# picoclick_c3t.net
KiCad netlist of a schematic drawn in EAGLE
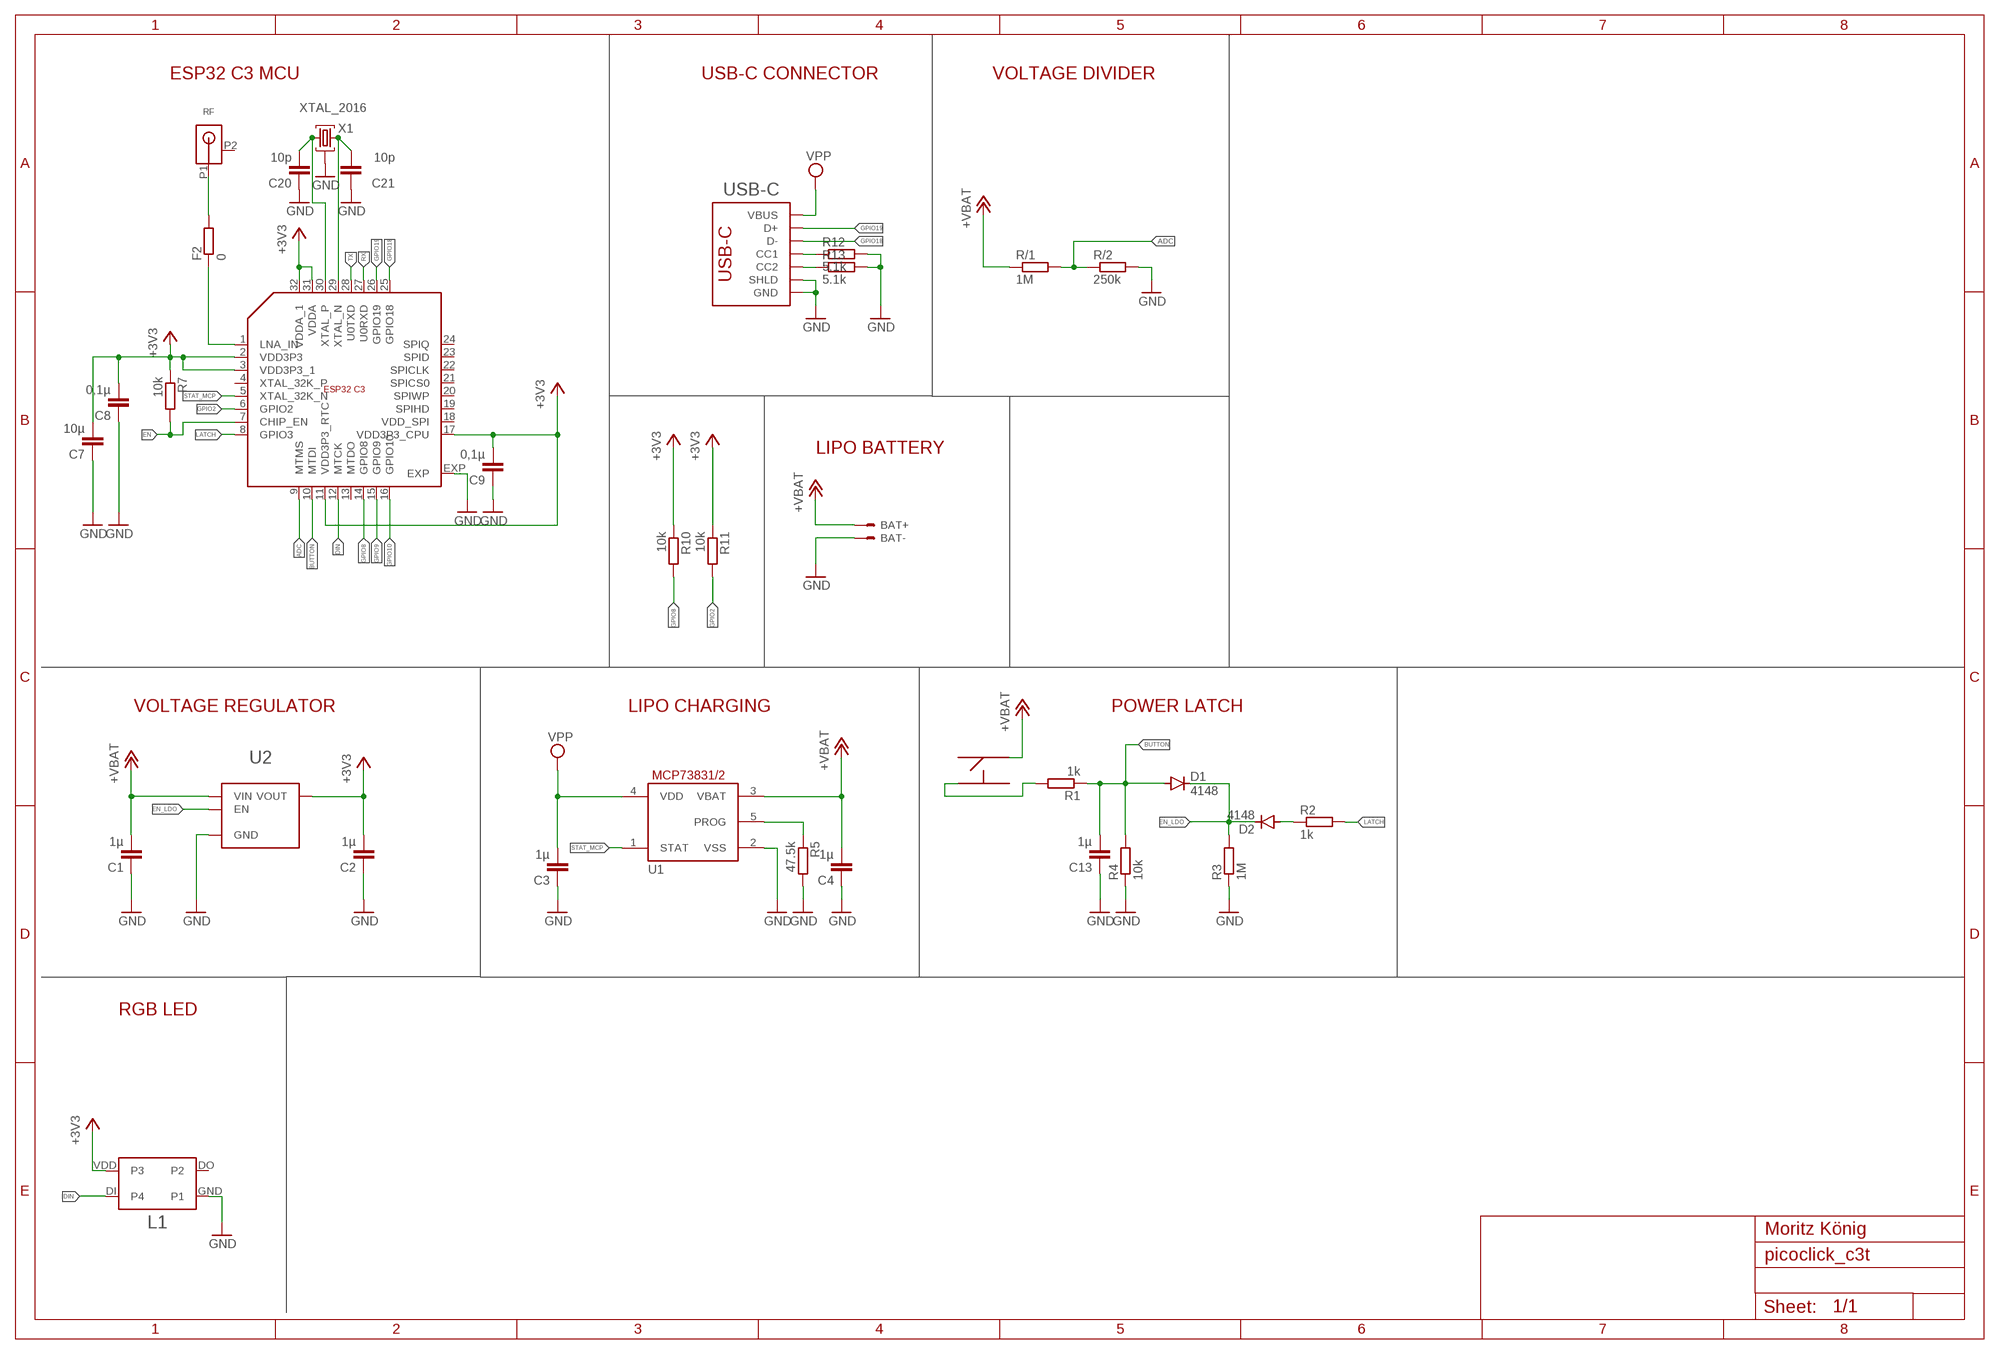
[diagram p0: schematic, sheet 1]

(export (version "E")
  (design (tool "Eeschema 10.0.6"))
  (components
    (comp (ref "BAT+")
      (value "TP/SP-1.5X1.0")
      (footprint "eagle-import:SOLDERPAD_1.5X1.0")
      (libsource (lib "eagle-import") (part "TP/SP-1.5X1.0"))
    )
    (comp (ref "BAT-")
      (value "TP/SP-1.5X1.0")
      (footprint "eagle-import:SOLDERPAD_1.5X1.0")
      (libsource (lib "eagle-import") (part "TP/SP-1.5X1.0"))
    )
    (comp (ref "C1")
      (value "1µ")
      (footprint "eagle-import:C0402_S")
      (libsource (lib "eagle-import") (part "C-EU-0402-WOKEEPOUT_S"))
    )
    (comp (ref "C2")
      (value "1µ")
      (footprint "eagle-import:C0402_S")
      (libsource (lib "eagle-import") (part "C-EU-0402-WOKEEPOUT_S"))
    )
    (comp (ref "C3")
      (value "1µ")
      (footprint "eagle-import:C0402_S")
      (libsource (lib "eagle-import") (part "C-EU-0402-WOKEEPOUT_S"))
    )
    (comp (ref "C4")
      (value "1µ")
      (footprint "eagle-import:C0402_S")
      (libsource (lib "eagle-import") (part "C-EU-0402-WOKEEPOUT_S"))
    )
    (comp (ref "C7")
      (value "10µ")
      (footprint "eagle-import:C0402_S")
      (libsource (lib "eagle-import") (part "C-EU-0402-WOKEEPOUT_S"))
    )
    (comp (ref "C8")
      (value "0,1µ")
      (footprint "eagle-import:C0402_S")
      (libsource (lib "eagle-import") (part "C-EU-0402-WOKEEPOUT_S"))
    )
    (comp (ref "C9")
      (value "0,1µ")
      (footprint "eagle-import:C0402_S")
      (libsource (lib "eagle-import") (part "C-EU-0402-WOKEEPOUT_S"))
    )
    (comp (ref "C13")
      (value "1µ")
      (footprint "eagle-import:C0402_S")
      (libsource (lib "eagle-import") (part "C-EU-0402-WOKEEPOUT_S"))
    )
    (comp (ref "C20")
      (value "10p")
      (footprint "eagle-import:C0402_S")
      (libsource (lib "eagle-import") (part "C-EU-0402-WOKEEPOUT_S"))
    )
    (comp (ref "C21")
      (value "10p")
      (footprint "eagle-import:C0402_S")
      (libsource (lib "eagle-import") (part "C-EU-0402-WOKEEPOUT_S"))
    )
    (comp (ref "D1")
      (value "4148")
      (footprint "eagle-import:SOD523")
      (libsource (lib "eagle-import") (part "DIODE-SOD523"))
    )
    (comp (ref "D2")
      (value "4148")
      (footprint "eagle-import:SOD523")
      (libsource (lib "eagle-import") (part "DIODE-SOD523"))
    )
    (comp (ref "ESP1")
      (value "ESP32_C3_QFN32")
      (footprint "eagle-import:QFN32")
      (libsource (lib "eagle-import") (part "ESP32_C3_QFN32"))
    )
    (comp (ref "F2")
      (value "0")
      (footprint "eagle-import:R0402")
      (libsource (lib "eagle-import") (part "R-EU-0402-WOKEEPOUT"))
    )
    (comp (ref "L1")
      (value "WS2812_2020")
      (footprint "eagle-import:WS2812_2020")
      (libsource (lib "eagle-import") (part "WS2812_2020"))
    )
    (comp (ref "R/1")
      (value "1M")
      (footprint "eagle-import:R0402")
      (libsource (lib "eagle-import") (part "R-EU-0402-WOKEEPOUT"))
    )
    (comp (ref "R/2")
      (value "250k")
      (footprint "eagle-import:R0402")
      (libsource (lib "eagle-import") (part "R-EU-0402-WOKEEPOUT"))
    )
    (comp (ref "R1")
      (value "1k")
      (footprint "eagle-import:R0402")
      (libsource (lib "eagle-import") (part "R-EU-0402-WOKEEPOUT"))
    )
    (comp (ref "R2")
      (value "1k")
      (footprint "eagle-import:R0402")
      (libsource (lib "eagle-import") (part "R-EU-0402-WOKEEPOUT"))
    )
    (comp (ref "R3")
      (value "1M")
      (footprint "eagle-import:R0402")
      (libsource (lib "eagle-import") (part "R-EU-0402-WOKEEPOUT"))
    )
    (comp (ref "R4")
      (value "10k")
      (footprint "eagle-import:R0402")
      (libsource (lib "eagle-import") (part "R-EU-0402-WOKEEPOUT"))
    )
    (comp (ref "R5")
      (value "47.5k")
      (footprint "eagle-import:R0402")
      (libsource (lib "eagle-import") (part "R-EU-0402-WOKEEPOUT"))
    )
    (comp (ref "R7")
      (value "10k")
      (footprint "eagle-import:R0402")
      (libsource (lib "eagle-import") (part "R-EU-0402-WOKEEPOUT"))
    )
    (comp (ref "R10")
      (value "10k")
      (footprint "eagle-import:R0402")
      (libsource (lib "eagle-import") (part "R-EU-0402-WOKEEPOUT"))
    )
    (comp (ref "R11")
      (value "10k")
      (footprint "eagle-import:R0402")
      (libsource (lib "eagle-import") (part "R-EU-0402-WOKEEPOUT"))
    )
    (comp (ref "R12")
      (value "5.1k")
      (footprint "eagle-import:R0402")
      (libsource (lib "eagle-import") (part "R-EU-0402-WOKEEPOUT"))
    )
    (comp (ref "R13")
      (value "5.1k")
      (footprint "eagle-import:R0402")
      (libsource (lib "eagle-import") (part "R-EU-0402-WOKEEPOUT"))
    )
    (comp (ref "RF")
      (value "ANT3216LL00R2400A")
      (footprint "eagle-import:ANT3216LL00R2400A")
      (libsource (lib "eagle-import") (part "ANT3216LL00R2400A"))
    )
    (comp (ref "U$1")
      (value "BUTTON_ST-1187-3")
      (footprint "eagle-import:BUTTON_ST-1187-3")
      (libsource (lib "eagle-import") (part "BUTTON_ST-1187-3"))
    )
    (comp (ref "U1")
      (value "BRCL4054BME")
      (footprint "eagle-import:SOT23-5")
      (libsource (lib "eagle-import") (part "MCP73831_SOT23_5"))
    )
    (comp (ref "U2")
      (value "MIC5504")
      (footprint "eagle-import:TDFN4")
      (libsource (lib "eagle-import") (part "MIC5504"))
    )
    (comp (ref "USB-C")
      (value "USB_C_C393939")
      (footprint "eagle-import:USBC_C393939")
      (libsource (lib "eagle-import") (part "USB_C_C393939"))
    )
    (comp (ref "X1")
      (value "XTAL_2016")
      (footprint "eagle-import:XTYL_2016")
      (libsource (lib "eagle-import") (part "XTAL_2016"))
    )
  )
  (nets
    (net (code "1") (name "+3V3") (class "Default")
      (node (ref "C2") (pin "P$2") (pinfunction "2_P$2") (pintype "passive"))
      (node (ref "C7") (pin "P$2") (pinfunction "2_P$2") (pintype "passive"))
      (node (ref "C8") (pin "P$2") (pinfunction "2_P$2") (pintype "passive"))
      (node (ref "C9") (pin "P$2") (pinfunction "2_P$2") (pintype "passive"))
      (node (ref "ESP1") (pin "11") (pinfunction "VDD3P3_RTC_11") (pintype "bidirectional"))
      (node (ref "ESP1") (pin "17") (pinfunction "VDD3P3_CPU_17") (pintype "bidirectional"))
      (node (ref "ESP1") (pin "2") (pinfunction "VDD3P3_2") (pintype "bidirectional"))
      (node (ref "ESP1") (pin "3") (pinfunction "VDD3P3_1_3") (pintype "bidirectional"))
      (node (ref "ESP1") (pin "31") (pinfunction "VDDA_31") (pintype "bidirectional"))
      (node (ref "ESP1") (pin "32") (pinfunction "VDDA_1_32") (pintype "bidirectional"))
      (node (ref "L1") (pin "VDD") (pinfunction "P3_VDD") (pintype "bidirectional"))
      (node (ref "R10") (pin "1") (pinfunction "1_1") (pintype "passive"))
      (node (ref "R11") (pin "1") (pinfunction "1_1") (pintype "passive"))
      (node (ref "R7") (pin "1") (pinfunction "1_1") (pintype "passive"))
      (node (ref "U2") (pin "P1") (pinfunction "VOUT_P1") (pintype "bidirectional"))
    )
    (net (code "2") (name "+VBAT") (class "Default")
      (node (ref "BAT+") (pin "1") (pinfunction "S_1") (pintype "passive"))
      (node (ref "C1") (pin "P$2") (pinfunction "2_P$2") (pintype "passive"))
      (node (ref "C4") (pin "P$2") (pinfunction "2_P$2") (pintype "passive"))
      (node (ref "R/1") (pin "1") (pinfunction "1_1") (pintype "passive"))
      (node (ref "U$1") (pin "P2") (pinfunction "P2_P2") (pintype "bidirectional"))
      (node (ref "U1") (pin "3") (pinfunction "VBAT_3") (pintype "bidirectional"))
      (node (ref "U2") (pin "P4") (pinfunction "VIN_P4") (pintype "bidirectional"))
    )
    (net (code "3") (name "ADC") (class "Default")
      (node (ref "ESP1") (pin "9") (pinfunction "MTMS_9") (pintype "bidirectional"))
      (node (ref "R/1") (pin "2") (pinfunction "2_2") (pintype "passive"))
      (node (ref "R/2") (pin "1") (pinfunction "1_1") (pintype "passive"))
    )
    (net (code "4") (name "BUTTON") (class "Default")
      (node (ref "C13") (pin "P$2") (pinfunction "2_P$2") (pintype "passive"))
      (node (ref "D1") (pin "A") (pinfunction "A_A") (pintype "passive"))
      (node (ref "ESP1") (pin "10") (pinfunction "MTDI_10") (pintype "bidirectional"))
      (node (ref "R1") (pin "1") (pinfunction "1_1") (pintype "passive"))
      (node (ref "R4") (pin "2") (pinfunction "2_2") (pintype "passive"))
    )
    (net (code "5") (name "DIN") (class "Default")
      (node (ref "ESP1") (pin "12") (pinfunction "MTCK_12") (pintype "bidirectional"))
      (node (ref "L1") (pin "DI") (pinfunction "P4_DI") (pintype "bidirectional"))
    )
    (net (code "6") (name "EN") (class "Default")
      (node (ref "ESP1") (pin "7") (pinfunction "CHIP_EN_7") (pintype "bidirectional"))
      (node (ref "R7") (pin "2") (pinfunction "2_2") (pintype "passive"))
    )
    (net (code "7") (name "EN_LDO") (class "Default")
      (node (ref "D1") (pin "C") (pinfunction "C_C") (pintype "passive"))
      (node (ref "D2") (pin "C") (pinfunction "C_C") (pintype "passive"))
      (node (ref "R3") (pin "2") (pinfunction "2_2") (pintype "passive"))
      (node (ref "U2") (pin "P3") (pinfunction "EN_P3") (pintype "bidirectional"))
    )
    (net (code "8") (name "GND") (class "Default")
      (node (ref "BAT-") (pin "1") (pinfunction "S_1") (pintype "passive"))
      (node (ref "C1") (pin "P$1") (pinfunction "1_P$1") (pintype "passive"))
      (node (ref "C13") (pin "P$1") (pinfunction "1_P$1") (pintype "passive"))
      (node (ref "C2") (pin "P$1") (pinfunction "1_P$1") (pintype "passive"))
      (node (ref "C20") (pin "P$1") (pinfunction "1_P$1") (pintype "passive"))
      (node (ref "C21") (pin "P$1") (pinfunction "1_P$1") (pintype "passive"))
      (node (ref "C3") (pin "P$1") (pinfunction "1_P$1") (pintype "passive"))
      (node (ref "C4") (pin "P$1") (pinfunction "1_P$1") (pintype "passive"))
      (node (ref "C7") (pin "P$1") (pinfunction "1_P$1") (pintype "passive"))
      (node (ref "C8") (pin "P$1") (pinfunction "1_P$1") (pintype "passive"))
      (node (ref "C9") (pin "P$1") (pinfunction "1_P$1") (pintype "passive"))
      (node (ref "ESP1") (pin "EXP") (pinfunction "EXP_EXP") (pintype "bidirectional"))
      (node (ref "L1") (pin "GND") (pinfunction "P1_GND") (pintype "bidirectional"))
      (node (ref "R/2") (pin "2") (pinfunction "2_2") (pintype "passive"))
      (node (ref "R12") (pin "2") (pinfunction "2_2") (pintype "passive"))
      (node (ref "R13") (pin "2") (pinfunction "2_2") (pintype "passive"))
      (node (ref "R3") (pin "1") (pinfunction "1_1") (pintype "passive"))
      (node (ref "R4") (pin "1") (pinfunction "1_1") (pintype "passive"))
      (node (ref "R5") (pin "2") (pinfunction "2_2") (pintype "passive"))
      (node (ref "U1") (pin "2") (pinfunction "VSS_2") (pintype "power_in"))
      (node (ref "U2") (pin "EXP") (pinfunction "GND_EXP") (pintype "bidirectional"))
      (node (ref "U2") (pin "P2") (pinfunction "GND_P2") (pintype "bidirectional"))
      (node (ref "USB-C") (pin "A1B12") (pinfunction "GND_A1B12") (pintype "bidirectional"))
      (node (ref "USB-C") (pin "B1A12") (pinfunction "GND_B1A12") (pintype "bidirectional"))
      (node (ref "USB-C") (pin "S1") (pinfunction "SHLD_S1") (pintype "bidirectional"))
      (node (ref "USB-C") (pin "S2") (pinfunction "SHLD_S2") (pintype "bidirectional"))
      (node (ref "USB-C") (pin "S3") (pinfunction "SHLD_S3") (pintype "bidirectional"))
      (node (ref "USB-C") (pin "S4") (pinfunction "SHLD_S4") (pintype "bidirectional"))
      (node (ref "X1") (pin "P2") (pinfunction "G_P2") (pintype "passive"))
      (node (ref "X1") (pin "P4") (pinfunction "G_P4") (pintype "passive"))
    )
    (net (code "9") (name "GPIO2") (class "Default")
      (node (ref "ESP1") (pin "6") (pinfunction "GPIO2_6") (pintype "bidirectional"))
      (node (ref "R11") (pin "2") (pinfunction "2_2") (pintype "passive"))
    )
    (net (code "10") (name "GPIO8") (class "Default")
      (node (ref "ESP1") (pin "14") (pinfunction "GPIO8_14") (pintype "bidirectional"))
      (node (ref "R10") (pin "2") (pinfunction "2_2") (pintype "passive"))
    )
    (net (code "11") (name "GPIO9") (class "Default")
      (node (ref "ESP1") (pin "15") (pinfunction "GPIO9_15") (pintype "bidirectional"))
    )
    (net (code "12") (name "GPIO10") (class "Default")
      (node (ref "ESP1") (pin "16") (pinfunction "GPIO10_16") (pintype "bidirectional"))
    )
    (net (code "13") (name "GPIO18") (class "Default")
      (node (ref "ESP1") (pin "25") (pinfunction "GPIO18_25") (pintype "bidirectional"))
      (node (ref "USB-C") (pin "A7") (pinfunction "D-_A7") (pintype "bidirectional"))
      (node (ref "USB-C") (pin "B7") (pinfunction "D-_B7") (pintype "bidirectional"))
    )
    (net (code "14") (name "GPIO19") (class "Default")
      (node (ref "ESP1") (pin "26") (pinfunction "GPIO19_26") (pintype "bidirectional"))
      (node (ref "USB-C") (pin "A6") (pinfunction "D+_A6") (pintype "bidirectional"))
      (node (ref "USB-C") (pin "B6") (pinfunction "D+_B6") (pintype "bidirectional"))
    )
    (net (code "15") (name "LATCH") (class "Default")
      (node (ref "ESP1") (pin "8") (pinfunction "GPIO3_8") (pintype "bidirectional"))
      (node (ref "R2") (pin "2") (pinfunction "2_2") (pintype "passive"))
    )
    (net (code "16") (name "Net-(C20-2)") (class "Default")
      (node (ref "C20") (pin "P$2") (pinfunction "2_P$2") (pintype "passive"))
      (node (ref "ESP1") (pin "30") (pinfunction "XTAL_P_30") (pintype "bidirectional"))
      (node (ref "X1") (pin "P1") (pinfunction "1_P1") (pintype "passive"))
    )
    (net (code "17") (name "Net-(C21-2)") (class "Default")
      (node (ref "C21") (pin "P$2") (pinfunction "2_P$2") (pintype "passive"))
      (node (ref "ESP1") (pin "29") (pinfunction "XTAL_N_29") (pintype "bidirectional"))
      (node (ref "X1") (pin "P3") (pinfunction "2_P3") (pintype "passive"))
    )
    (net (code "18") (name "Net-(D2-PadA)") (class "Default")
      (node (ref "D2") (pin "A") (pinfunction "A_A") (pintype "passive"))
      (node (ref "R2") (pin "1") (pinfunction "1_1") (pintype "passive"))
    )
    (net (code "19") (name "Net-(ESP1-LNA_IN)") (class "Default")
      (node (ref "ESP1") (pin "1") (pinfunction "LNA_IN_1") (pintype "bidirectional"))
      (node (ref "F2") (pin "1") (pinfunction "1_1") (pintype "passive"))
    )
    (net (code "20") (name "Net-(R1-Pad2)") (class "Default")
      (node (ref "R1") (pin "2") (pinfunction "2_2") (pintype "passive"))
      (node (ref "U$1") (pin "P3") (pinfunction "P3_P3") (pintype "bidirectional"))
    )
    (net (code "21") (name "Net-(RF-ANT)") (class "Default")
      (node (ref "F2") (pin "2") (pinfunction "2_2") (pintype "passive"))
      (node (ref "RF") (pin "P1") (pinfunction "ANT_P1") (pintype "bidirectional"))
    )
    (net (code "22") (name "Net-(U1-PROG)") (class "Default")
      (node (ref "R5") (pin "1") (pinfunction "1_1") (pintype "passive"))
      (node (ref "U1") (pin "5") (pinfunction "PROG_5") (pintype "input"))
    )
    (net (code "23") (name "Net-(USB-C-CC1)") (class "Default")
      (node (ref "R12") (pin "1") (pinfunction "1_1") (pintype "passive"))
      (node (ref "USB-C") (pin "A5") (pinfunction "CC1_A5") (pintype "bidirectional"))
    )
    (net (code "24") (name "Net-(USB-C-CC2)") (class "Default")
      (node (ref "R13") (pin "1") (pinfunction "1_1") (pintype "passive"))
      (node (ref "USB-C") (pin "B5") (pinfunction "CC2_B5") (pintype "bidirectional"))
    )
    (net (code "25") (name "RX") (class "Default")
      (node (ref "ESP1") (pin "27") (pinfunction "U0RXD_27") (pintype "bidirectional"))
    )
    (net (code "26") (name "STAT_MCP") (class "Default")
      (node (ref "ESP1") (pin "5") (pinfunction "XTAL_32K_N_5") (pintype "bidirectional"))
      (node (ref "U1") (pin "1") (pinfunction "STAT_1") (pintype "output"))
    )
    (net (code "27") (name "TX") (class "Default")
      (node (ref "ESP1") (pin "28") (pinfunction "U0TXD_28") (pintype "bidirectional"))
    )
    (net (code "28") (name "VPP") (class "Default")
      (node (ref "C3") (pin "P$2") (pinfunction "2_P$2") (pintype "passive"))
      (node (ref "U1") (pin "4") (pinfunction "VDD_4") (pintype "power_in"))
      (node (ref "USB-C") (pin "A4B9") (pinfunction "VBUS_A4B9") (pintype "bidirectional"))
      (node (ref "USB-C") (pin "B4A9") (pinfunction "VBUS_B4A9") (pintype "bidirectional"))
    )
    (net (code "29") (name "unconnected-(ESP1-MTDO-Pad13)") (class "Default")
      (node (ref "ESP1") (pin "13") (pinfunction "MTDO_13") (pintype "bidirectional"))
    )
    (net (code "30") (name "unconnected-(ESP1-SPICLK-Pad22)") (class "Default")
      (node (ref "ESP1") (pin "22") (pinfunction "SPICLK_22") (pintype "bidirectional"))
    )
    (net (code "31") (name "unconnected-(ESP1-SPICS0-Pad21)") (class "Default")
      (node (ref "ESP1") (pin "21") (pinfunction "SPICS0_21") (pintype "bidirectional"))
    )
    (net (code "32") (name "unconnected-(ESP1-SPID-Pad23)") (class "Default")
      (node (ref "ESP1") (pin "23") (pinfunction "SPID_23") (pintype "bidirectional"))
    )
    (net (code "33") (name "unconnected-(ESP1-SPIHD-Pad19)") (class "Default")
      (node (ref "ESP1") (pin "19") (pinfunction "SPIHD_19") (pintype "bidirectional"))
    )
    (net (code "34") (name "unconnected-(ESP1-SPIQ-Pad24)") (class "Default")
      (node (ref "ESP1") (pin "24") (pinfunction "SPIQ_24") (pintype "bidirectional"))
    )
    (net (code "35") (name "unconnected-(ESP1-SPIWP-Pad20)") (class "Default")
      (node (ref "ESP1") (pin "20") (pinfunction "SPIWP_20") (pintype "bidirectional"))
    )
    (net (code "36") (name "unconnected-(ESP1-VDD_SPI-Pad18)") (class "Default")
      (node (ref "ESP1") (pin "18") (pinfunction "VDD_SPI_18") (pintype "bidirectional"))
    )
    (net (code "37") (name "unconnected-(ESP1-XTAL_32K_P-Pad4)") (class "Default")
      (node (ref "ESP1") (pin "4") (pinfunction "XTAL_32K_P_4") (pintype "bidirectional"))
    )
    (net (code "38") (name "unconnected-(L1-P2-PadDO)") (class "Default")
      (node (ref "L1") (pin "DO") (pinfunction "P2_DO") (pintype "bidirectional"))
    )
    (net (code "39") (name "unconnected-(RF-GND-PadP2)") (class "Default")
      (node (ref "RF") (pin "P2") (pinfunction "GND_P2") (pintype "bidirectional"))
    )
    (net (code "40") (name "unconnected-(U$1-PadP1)") (class "Default")
      (node (ref "U$1") (pin "P1") (pinfunction "P1_P1") (pintype "bidirectional"))
    )
    (net (code "41") (name "unconnected-(U$1-PadP4)") (class "Default")
      (node (ref "U$1") (pin "P4") (pinfunction "P4_P4") (pintype "bidirectional"))
    )
  )
)
